# EVSE_Control_and_GFCI.net
KiCad netlist of a schematic drawn in Altium Designer
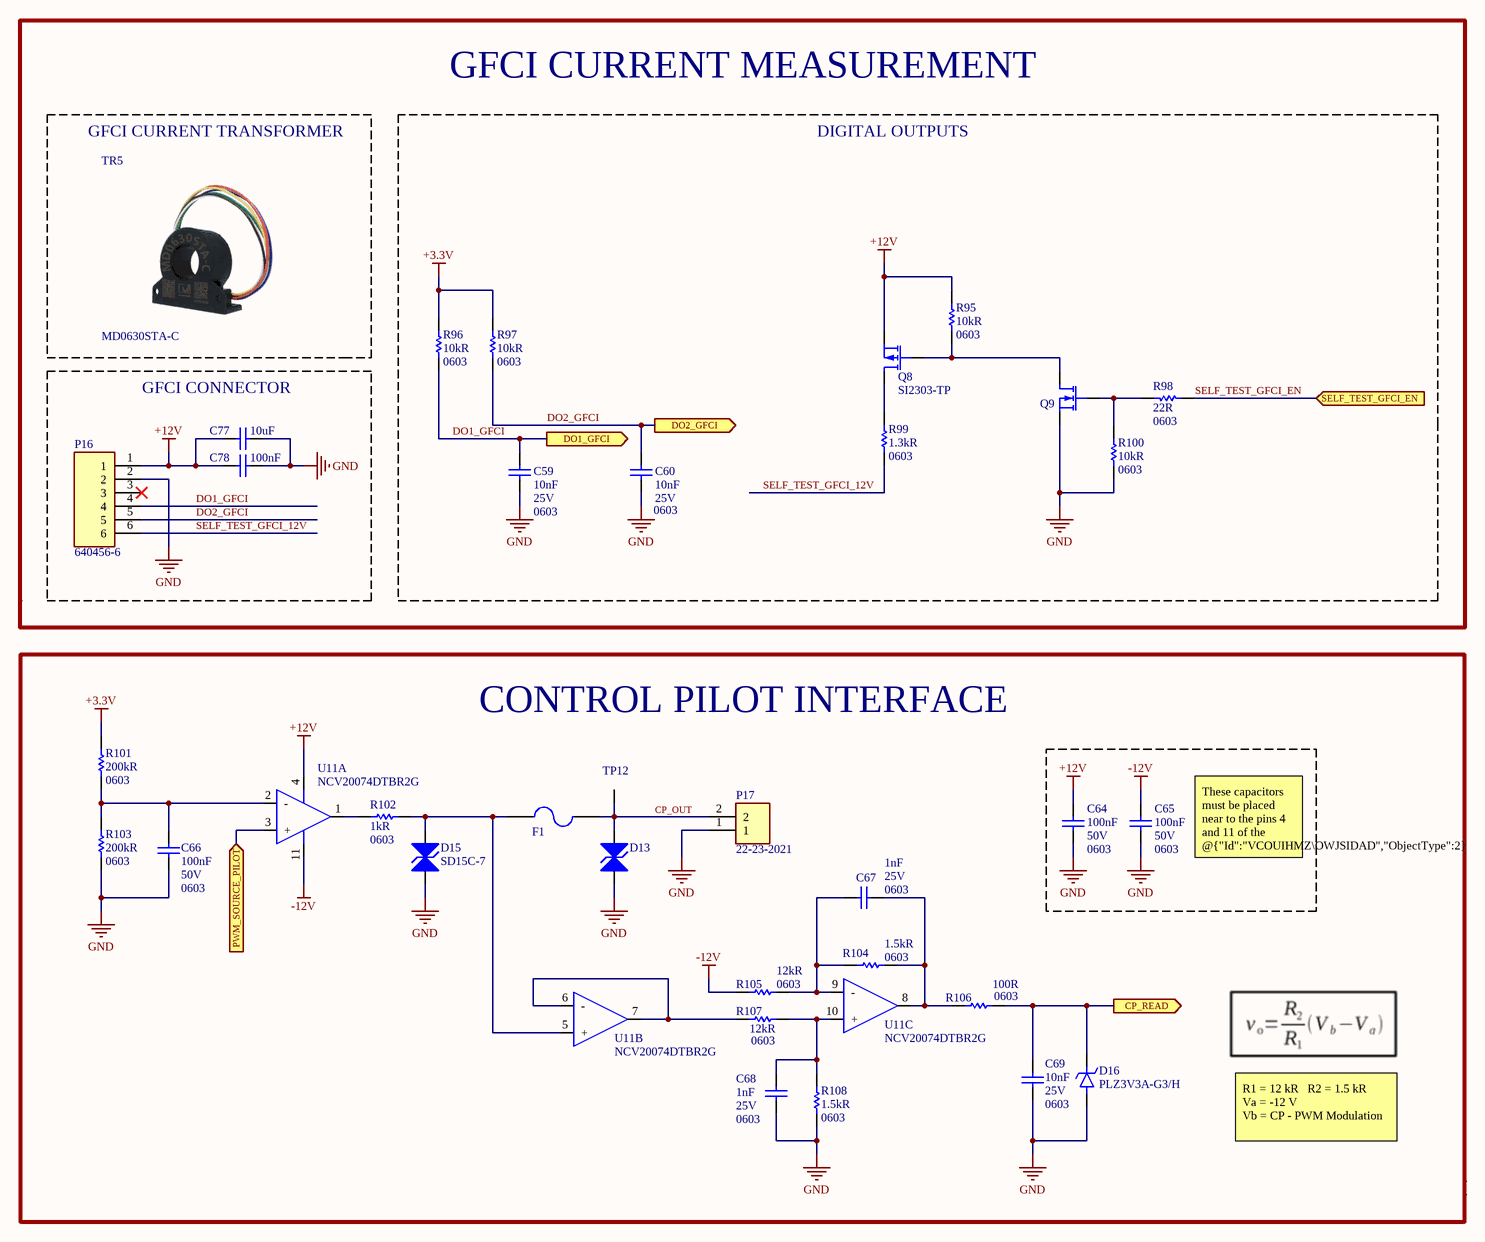
[diagram p0: EVSE Control and GFCI.SchDoc]

(export (version "E")
  (design (tool "Eeschema 10.0.6"))
  (components
    (comp (ref "C59")
      (value "C_0603_0.01uF_25V_10%")
      (footprint "C0603")
      (description "Surface Mount Ceramic Multilayer Capacitor 0.01uF 10% X7R 25V 0603 Paper T/R")
      (fields
        (field (name "MANUFACTURER") "Yageo")
        (field (name "MANUFACTURER PART NUMBER") "CC0603KRX7R8BB103")
        (field (name "VOLTAGE RATING") "25V")
        (field (name "CAPACITANCE") "10nF")
        (field (name "CASE CODE (IMPERIAL)") "0603")
      )
      (libsource (lib "Power2Go - REV05") (part "C_0603_0.01uF_25V_10%"))
    )
    (comp (ref "C60")
      (value "C_0603_0.01uF_25V_10%")
      (footprint "C0603")
      (description "Surface Mount Ceramic Multilayer Capacitor 0.01uF 10% X7R 25V 0603 Paper T/R")
      (fields
        (field (name "MANUFACTURER") "Yageo")
        (field (name "MANUFACTURER PART NUMBER") "CC0603KRX7R8BB103")
        (field (name "VOLTAGE RATING") "25V")
        (field (name "CAPACITANCE") "10nF")
        (field (name "CASE CODE (IMPERIAL)") "0603")
      )
      (libsource (lib "Power2Go - REV05") (part "C_0603_0.01uF_25V_10%"))
    )
    (comp (ref "C64")
      (value "100nF")
      (footprint "C0603")
      (description "Cap Ceramic 50V 20% +Tol 20% -Tol X7R 15% TC 0.1uF SMD 0603")
      (fields
        (field (name "MANUFACTURER") "Yageo")
        (field (name "MANUFACTURER PART NUMBER") "CC0603MRX7R9BB104")
        (field (name "CASE/PACKAGE") "0603")
        (field (name "VOLTAGE RATING") "50V")
      )
      (libsource (lib "Power2Go - REV05") (part "C_0603_0.1uF_50V_20%"))
    )
    (comp (ref "C65")
      (value "100nF")
      (footprint "C0603")
      (description "Cap Ceramic 50V 20% +Tol 20% -Tol X7R 15% TC 0.1uF SMD 0603")
      (fields
        (field (name "MANUFACTURER") "Yageo")
        (field (name "MANUFACTURER PART NUMBER") "CC0603MRX7R9BB104")
        (field (name "CASE/PACKAGE") "0603")
        (field (name "VOLTAGE RATING") "50V")
      )
      (libsource (lib "Power2Go - REV05") (part "C_0603_0.1uF_50V_20%"))
    )
    (comp (ref "C66")
      (value "100nF")
      (footprint "C0603")
      (description "Cap Ceramic 50V 20% +Tol 20% -Tol X7R 15% TC 0.1uF SMD 0603")
      (fields
        (field (name "MANUFACTURER") "Yageo")
        (field (name "MANUFACTURER PART NUMBER") "CC0603MRX7R9BB104")
        (field (name "CASE/PACKAGE") "0603")
        (field (name "VOLTAGE RATING") "50V")
      )
      (libsource (lib "Power2Go - REV05") (part "C_0603_0.1uF_50V_20%"))
    )
    (comp (ref "C67")
      (value "1nF")
      (footprint "C0603")
      (description "0603 C 1nF Ceramic Multilayer Capacitor; 25 VDC; +125degC; C0G Dielectric; +/-5%")
      (fields
        (field (name "MANUFACTURER") "KEMET")
        (field (name "MANUFACTURER PART NUMBER") "C0603C102J3GACTU")
        (field (name "VOLTAGE RATING") "25V")
        (field (name "CASE CODE (IMPERIAL)") "0603")
      )
      (libsource (lib "Power2Go - REV05") (part "C_0603_1000pF_25V_5%"))
    )
    (comp (ref "C68")
      (value "1nF")
      (footprint "C0603")
      (description "0603 C 1nF Ceramic Multilayer Capacitor; 25 VDC; +125degC; C0G Dielectric; +/-5%")
      (fields
        (field (name "MANUFACTURER") "KEMET")
        (field (name "MANUFACTURER PART NUMBER") "C0603C102J3GACTU")
        (field (name "VOLTAGE RATING") "25V")
        (field (name "CASE CODE (IMPERIAL)") "0603")
      )
      (libsource (lib "Power2Go - REV05") (part "C_0603_1000pF_25V_5%"))
    )
    (comp (ref "C69")
      (value "C_0603_0.01uF_25V_10%")
      (footprint "C0603")
      (description "Surface Mount Ceramic Multilayer Capacitor 0.01uF 10% X7R 25V 0603 Paper T/R")
      (fields
        (field (name "MANUFACTURER") "Yageo")
        (field (name "MANUFACTURER PART NUMBER") "CC0603KRX7R8BB103")
        (field (name "VOLTAGE RATING") "25V")
        (field (name "CAPACITANCE") "10nF")
        (field (name "CASE CODE (IMPERIAL)") "0603")
      )
      (libsource (lib "Power2Go - REV05") (part "C_0603_0.01uF_25V_10%"))
    )
    (comp (ref "C77")
      (value "C_0603_10uF_35V_20%")
      (footprint "C0603")
      (description "Cap Ceramic 10uF 35V X5R 20% Pad SMD 0603 85C T/R")
      (fields
        (field (name "MANUFACTURER") "Murata")
        (field (name "MANUFACTURER PART NUMBER") "GRM188R6YA106MA73D")
        (field (name "CAPACITANCE") "10uF")
      )
      (libsource (lib "Power2Go - REV05") (part "C_0603_10uF_35V_20%"))
    )
    (comp (ref "C78")
      (value "100nF")
      (footprint "C0603")
      (description "Cap Ceramic 50V 20% +Tol 20% -Tol X7R 15% TC 0.1uF SMD 0603")
      (fields
        (field (name "MANUFACTURER") "Yageo")
        (field (name "MANUFACTURER PART NUMBER") "CC0603MRX7R9BB104")
      )
      (libsource (lib "Power2Go - REV05") (part "C_0603_0.1uF_50V_20%"))
    )
    (comp (ref "D13")
      (value "SM30T15CAY")
      (footprint "DO-214AB-2")
      (description "Trans Voltage Suppressor Diode, 3000W, 13V V(RWM), Bidirectional, 1 Element, Silicon, DO-214AB")
      (fields (field (name "MANUFACTURER") "STMicroelectronics"))
      (libsource (lib "Power2Go - REV05") (part "D_TVS_SM30T15CAY"))
    )
    (comp (ref "D15")
      (value "SD15C-7")
      (footprint "SOD323")
      (description "TVS Diode Bi-Directional 16.7V 12A 320W 2-Pin SOD-323 T/R")
      (fields (field (name "MANUFACTURER") "Diodes") (field (name "MANUFACTURER PART NUMBER") "SD15C-7"))
      (libsource (lib "Power2Go - REV05") (part "D_TVS_SD15C-7"))
    )
    (comp (ref "D16")
      (value "PLZ3V3A-G3/H")
      (footprint "DO-219AC-2")
      (description "Zener Diode Microsmf Do219Ac2.5%, 3.3V (3.16V - 3.38V), 0.5W")
      (fields (field (name "MANUFACTURER") "Vishay") (field (name "MANUFACTURER PART NUMBER") "PLZ3V3A-G3/H"))
      (libsource (lib "Power2Go - REV05") (part "D_Zenner_PLZ3V3A-G3/H"))
    )
    (comp (ref "F1")
      (value "0ZCM0002FF2G")
      (footprint "F0603")
      (description "PTC Resettable Fuse, 60V, 12ohm, Surface Mount")
      (fields (field (name "MANUFACTURER") "Bel"))
      (libsource (lib "Power2Go - REV05") (part "F_0ZCM0002FF2G_0603"))
    )
    (comp (ref "P16")
      (value "640456-6")
      (footprint "HEADER_2.54MM_6POS_PTH")
      (description "Connector Wire to Board Header 6 Position 2.54mm Solder Straight Thru-Hole")
      (fields
        (field (name "MANUFACTURER") "TE Connectivity")
        (field (name "SUPPLIER PART NUMBER 1") "640456-6")
      )
      (libsource (lib "Power2Go - REV05") (part "P_HEADER_6POS_2.54MM_PTH"))
    )
    (comp (ref "P17")
      (value "22-23-2021")
      (footprint "HEADER_KK_2.54MM_2POS")
      (description "KK 254 Solid Header, Vertical, with Friction Lock, 2 Circuits, Tin (Sn) Plating")
      (fields (field (name "MANUFACTURER") "Molex") (field (name "MANUFACTURER PART NUMBER") "22-23-2021"))
      (libsource (lib "Power2Go - REV05") (part "P_Molex_HEADER_2POS_2.54MM_PTH"))
    )
    (comp (ref "Q8")
      (value "SI2303-TP")
      (footprint "SOT23")
      (description "Sample Fpn Only - P-channel Mosfet, SOT-23 Package")
      (fields (field (name "MANUFACTURER") "MCC") (field (name "MANUFACTURER PART NUMBER") "SI2303-TP"))
      (libsource (lib "Power2Go - REV05") (part "Q_PMOS_SI2303-TP"))
    )
    (comp (ref "Q9")
      (value "RSF015N06FRATL")
      (footprint "TUMT-3")
      (description "Transistor Mosfet N-ch 60V 1.5A 3-PIN Tumt T/r")
      (fields (field (name "MANUFACTURER") "Rohm"))
      (libsource (lib "Power2Go - REV05") (part "Q_RSF015N06FRATL_TUMT-3"))
    )
    (comp (ref "R95")
      (value "10kR")
      (footprint "R0603")
      (fields
        (field (name "MANUFACTURER") "Vishay")
        (field (name "MANUFACTURER PART NUMBER") "CRCW060310K0JNEBC")
        (field (name "TOLERANCE") "5%")
        (field (name "CASE/PACKAGE") "0603")
      )
      (libsource (lib "Power2Go - REV05") (part "R_0603_10kR_5%_1/10W"))
    )
    (comp (ref "R96")
      (value "10kR")
      (footprint "R0603")
      (fields
        (field (name "MANUFACTURER") "Vishay")
        (field (name "MANUFACTURER PART NUMBER") "CRCW060310K0JNEBC")
        (field (name "TOLERANCE") "5%")
        (field (name "CASE/PACKAGE") "0603")
      )
      (libsource (lib "Power2Go - REV05") (part "R_0603_10kR_5%_1/10W"))
    )
    (comp (ref "R97")
      (value "10kR")
      (footprint "R0603")
      (fields
        (field (name "MANUFACTURER") "Vishay")
        (field (name "MANUFACTURER PART NUMBER") "CRCW060310K0JNEBC")
        (field (name "TOLERANCE") "5%")
        (field (name "CASE/PACKAGE") "0603")
      )
      (libsource (lib "Power2Go - REV05") (part "R_0603_10kR_5%_1/10W"))
    )
    (comp (ref "R98")
      (value "CRCW060322R0FKEAC")
      (footprint "R0603")
      (description "Thick Film Resistors - SMD 1/10Watt 22ohms 1% Commercial Use")
      (fields
        (field (name "MANUFACTURER") "Vishay")
        (field (name "TOLERANCE") "1%")
        (field (name "RESISTANCE") "22R")
        (field (name "CASE CODE (IMPERIAL)") "0603")
      )
      (libsource (lib "Power2Go - REV05") (part "R_0603_22R_1%_1/10W"))
    )
    (comp (ref "R99")
      (value "1.3kR")
      (footprint "R0603")
      (description "SMD Chip Resistor, 1.3 kOhm, ± 1%, 250 mW, 0603 [1608 Metric], Thick Film, Anti-Surge")
      (fields
        (field (name "MANUFACTURER") "Panasonic")
        (field (name "TOLERANCE") "1%")
        (field (name "CASE CODE (IMPERIAL)") "0603")
      )
      (libsource (lib "Power2Go - REV05") (part "R_0603_1.3kR_1%_1/4W"))
    )
    (comp (ref "R100")
      (value "10kR")
      (footprint "R0603")
      (fields
        (field (name "MANUFACTURER") "Vishay")
        (field (name "MANUFACTURER PART NUMBER") "CRCW060310K0JNEBC")
        (field (name "TOLERANCE") "5%")
        (field (name "CASE/PACKAGE") "0603")
      )
      (libsource (lib "Power2Go - REV05") (part "R_0603_10kR_5%_1/10W"))
    )
    (comp (ref "R101")
      (value "200kR")
      (footprint "R0603")
      (description "Res Thin Film 0603 200K Ohm 1% 1/10W ±25ppm/°C Molded SMD Paper T/R")
      (fields
        (field (name "MANUFACTURER") "Yageo")
        (field (name "MANUFACTURER PART NUMBER") "RT0603FRD07200KL")
        (field (name "CASE/PACKAGE") "0603")
      )
      (libsource (lib "Power2Go - REV05") (part "R_0603_200kR_1%_1/10W_25PPM"))
    )
    (comp (ref "R102")
      (value "1kR")
      (footprint "R0603")
      (description "RES SMD 1K OHM 1% 1/10W 0603")
      (fields
        (field (name "MANUFACTURER") "Bourns")
        (field (name "MANUFACTURER PART NUMBER") "CRT0603-FY-1001ELF")
        (field (name "CASE/PACKAGE") "0603")
      )
      (libsource (lib "Power2Go - REV05") (part "R_0603_1kR_1%_1/10W_25PPM"))
    )
    (comp (ref "R103")
      (value "200kR")
      (footprint "R0603")
      (description "Res Thin Film 0603 200K Ohm 1% 1/10W ±25ppm/°C Molded SMD Paper T/R")
      (fields
        (field (name "MANUFACTURER") "Yageo")
        (field (name "MANUFACTURER PART NUMBER") "RT0603FRD07200KL")
        (field (name "CASE/PACKAGE") "0603")
      )
      (libsource (lib "Power2Go - REV05") (part "R_0603_200kR_1%_1/10W_25PPM"))
    )
    (comp (ref "R104")
      (value "1.5kR")
      (footprint "R0603")
      (description "Res 1.5K Ohm 1% 1/10W 0603")
      (fields
        (field (name "MANUFACTURER") "KOA Speer")
        (field (name "MANUFACTURER PART NUMBER") "RN73H1JTTD1501F25")
        (field (name "CASE CODE (IMPERIAL)") "0603")
      )
      (libsource (lib "Power2Go - REV05") (part "R_0603_1.5kR_1%_1/10W_25PPM"))
    )
    (comp (ref "R105")
      (value "12kR")
      (footprint "R0603")
      (description "Res Thin Film 0603 12K Ohm 0.5% 1/10W ±25ppm/°C Molded SMD SMD Paper T/R")
      (fields
        (field (name "MANUFACTURER") "Yageo")
        (field (name "MANUFACTURER PART NUMBER") "RT0603DRD0712KL")
        (field (name "CASE CODE (IMPERIAL)") "0603")
      )
      (libsource (lib "Power2Go - REV05") (part "R_0603_12kR_0.5%_1/10W_25PPM"))
    )
    (comp (ref "R106")
      (value "100R")
      (footprint "R0603")
      (description "Res Thin Film 0603 100 Ohm 1% 1/10W ±25ppm/°C Molded SMD Paper Tape on Plastic Reel")
      (fields
        (field (name "MANUFACTURER") "Bourns")
        (field (name "MANUFACTURER PART NUMBER") "CRT0603-FY-1000ELF")
        (field (name "CASE/PACKAGE") "0603")
      )
      (libsource (lib "Power2Go - REV05") (part "R_0603_100R_1%_1/10W_25PPM"))
    )
    (comp (ref "R107")
      (value "12kR")
      (footprint "R0603")
      (description "Res Thin Film 0603 12K Ohm 0.5% 1/10W ±25ppm/°C Molded SMD SMD Paper T/R")
      (fields
        (field (name "MANUFACTURER") "Yageo")
        (field (name "MANUFACTURER PART NUMBER") "RT0603DRD0712KL")
        (field (name "CASE CODE (IMPERIAL)") "0603")
      )
      (libsource (lib "Power2Go - REV05") (part "R_0603_12kR_0.5%_1/10W_25PPM"))
    )
    (comp (ref "R108")
      (value "1.5kR")
      (footprint "R0603")
      (description "Res 1.5K Ohm 1% 1/10W 0603")
      (fields
        (field (name "MANUFACTURER") "KOA Speer")
        (field (name "MANUFACTURER PART NUMBER") "RN73H1JTTD1501F25")
        (field (name "CASE CODE (IMPERIAL)") "0603")
      )
      (libsource (lib "Power2Go - REV05") (part "R_0603_1.5kR_1%_1/10W_25PPM"))
    )
    (comp (ref "TP12")
      (value "S2761-46R")
      (footprint "TP_S276146R")
      (fields (field (name "MANUFACTURER") "Harwin"))
      (libsource (lib "Power2Go - REV05") (part "TP_S2761-46R_SMT"))
    )
    (comp (ref "TR5")
      (value "MD0630STA-C")
      (footprint "TC_MD0630STA-C")
      (description "MD36da-P Costly Evse B-Type RCD CT 6mA DC Residual Direct Current Detecting Device Sensor")
      (fields (field (name "MANUFACTER PART NUMBER") "MD0630STA-C"))
      (libsource (lib "Power2Go - REV05") (part "TR_MD0630STA-C"))
    )
    (comp (ref "U11")
      (value "NCV20074DTBR2G")
      (footprint "TSSOP-14")
      (description "Operational Amplifier, Wide supply range, 3 MHz CMOS Op-Amp")
      (fields
        (field (name "MANUFACTURER") "ON Semiconductor")
        (field (name "SUPPLIER PART NUMBER 1") "NCV20074DTBR2G")
      )
      (libsource (lib "Power2Go - REV05") (part "U_NCV20074DTBR2G_TSSOP-14"))
    )
  )
  (nets
    (net (code "1") (name "+3.3V") (class "Default")
      (node (ref "R101") (pin "1") (pinfunction "1_1") (pintype "passive"))
      (node (ref "R96") (pin "2") (pinfunction "2_2") (pintype "passive"))
      (node (ref "R97") (pin "2") (pinfunction "2_2") (pintype "passive"))
    )
    (net (code "2") (name "+12V") (class "Default")
      (node (ref "C64") (pin "1") (pinfunction "1_1") (pintype "passive"))
      (node (ref "C77") (pin "2") (pinfunction "2_2") (pintype "passive"))
      (node (ref "C78") (pin "2") (pinfunction "2_2") (pintype "passive"))
      (node (ref "P16") (pin "1") (pinfunction "1_1") (pintype "passive"))
      (node (ref "Q8") (pin "2") (pinfunction "S_2") (pintype "passive"))
      (node (ref "R95") (pin "2") (pinfunction "2_2") (pintype "passive"))
      (node (ref "U11") (pin "4") (pinfunction "V+_4") (pintype "passive"))
    )
    (net (code "3") (name "-12V") (class "Default")
      (node (ref "C65") (pin "1") (pinfunction "1_1") (pintype "passive"))
      (node (ref "R105") (pin "1") (pinfunction "1_1") (pintype "passive"))
      (node (ref "U11") (pin "11") (pinfunction "V-_11") (pintype "passive"))
    )
    (net (code "4") (name "/CP_OUT") (class "Default")
      (node (ref "D13") (pin "2") (pinfunction "2_2") (pintype "passive"))
      (node (ref "F1") (pin "2") (pinfunction "2_2") (pintype "passive"))
      (node (ref "P17") (pin "2") (pinfunction "2_2") (pintype "passive"))
      (node (ref "TP12") (pin "1") (pinfunction "1_1") (pintype "passive"))
    )
    (net (code "5") (name "/CP_READ") (class "Default")
      (node (ref "C69") (pin "1") (pinfunction "1_1") (pintype "passive"))
      (node (ref "D16") (pin "1") (pinfunction "K_1") (pintype "passive"))
      (node (ref "R106") (pin "2") (pinfunction "2_2") (pintype "passive"))
    )
    (net (code "6") (name "/DO1_GFCI") (class "Default")
      (node (ref "C59") (pin "2") (pinfunction "2_2") (pintype "passive"))
      (node (ref "P16") (pin "4") (pinfunction "4_4") (pintype "passive"))
      (node (ref "R96") (pin "1") (pinfunction "1_1") (pintype "passive"))
    )
    (net (code "7") (name "/DO2_GFCI") (class "Default")
      (node (ref "C60") (pin "2") (pinfunction "2_2") (pintype "passive"))
      (node (ref "P16") (pin "5") (pinfunction "5_5") (pintype "passive"))
      (node (ref "R97") (pin "1") (pinfunction "1_1") (pintype "passive"))
    )
    (net (code "8") (name "/PWM_SOURCE_PILOT") (class "Default")
      (node (ref "U11") (pin "3") (pinfunction "+_3") (pintype "passive"))
    )
    (net (code "9") (name "/SELF_TEST_GFCI_12V") (class "Default")
      (node (ref "P16") (pin "6") (pinfunction "6_6") (pintype "passive"))
      (node (ref "R99") (pin "1") (pinfunction "1_1") (pintype "passive"))
    )
    (net (code "10") (name "/SELF_TEST_GFCI_EN") (class "Default")
      (node (ref "R98") (pin "2") (pinfunction "2_2") (pintype "passive"))
    )
    (net (code "11") (name "GND") (class "Default")
      (node (ref "C59") (pin "1") (pinfunction "1_1") (pintype "passive"))
      (node (ref "C60") (pin "1") (pinfunction "1_1") (pintype "passive"))
      (node (ref "C64") (pin "2") (pinfunction "2_2") (pintype "passive"))
      (node (ref "C65") (pin "2") (pinfunction "2_2") (pintype "passive"))
      (node (ref "C66") (pin "2") (pinfunction "2_2") (pintype "passive"))
      (node (ref "C68") (pin "1") (pinfunction "1_1") (pintype "passive"))
      (node (ref "C69") (pin "2") (pinfunction "2_2") (pintype "passive"))
      (node (ref "C77") (pin "1") (pinfunction "1_1") (pintype "passive"))
      (node (ref "C78") (pin "1") (pinfunction "1_1") (pintype "passive"))
      (node (ref "D13") (pin "1") (pinfunction "1_1") (pintype "passive"))
      (node (ref "D15") (pin "1") (pinfunction "1_1") (pintype "passive"))
      (node (ref "D16") (pin "2") (pinfunction "A_2") (pintype "passive"))
      (node (ref "P16") (pin "2") (pinfunction "2_2") (pintype "passive"))
      (node (ref "P17") (pin "1") (pinfunction "1_1") (pintype "passive"))
      (node (ref "Q9") (pin "2") (pinfunction "S_2") (pintype "passive"))
      (node (ref "R100") (pin "1") (pinfunction "1_1") (pintype "passive"))
      (node (ref "R103") (pin "2") (pinfunction "2_2") (pintype "passive"))
      (node (ref "R108") (pin "2") (pinfunction "2_2") (pintype "passive"))
    )
    (net (code "12") (name "Net-(Q8-D)") (class "Default")
      (node (ref "Q8") (pin "3") (pinfunction "D_3") (pintype "passive"))
      (node (ref "R99") (pin "2") (pinfunction "2_2") (pintype "passive"))
    )
    (net (code "13") (name "Net-(Q8-G)") (class "Default")
      (node (ref "Q8") (pin "1") (pinfunction "G_1") (pintype "passive"))
      (node (ref "Q9") (pin "3") (pinfunction "D_3") (pintype "passive"))
      (node (ref "R95") (pin "1") (pinfunction "1_1") (pintype "passive"))
    )
    (net (code "14") (name "Net-(Q9-G)") (class "Default")
      (node (ref "Q9") (pin "1") (pinfunction "G_1") (pintype "passive"))
      (node (ref "R100") (pin "2") (pinfunction "2_2") (pintype "passive"))
      (node (ref "R98") (pin "1") (pinfunction "1_1") (pintype "passive"))
    )
    (net (code "15") (name "Net-(U11A--)") (class "Default")
      (node (ref "C66") (pin "1") (pinfunction "1_1") (pintype "passive"))
      (node (ref "R101") (pin "2") (pinfunction "2_2") (pintype "passive"))
      (node (ref "R103") (pin "1") (pinfunction "1_1") (pintype "passive"))
      (node (ref "U11") (pin "2") (pinfunction "-_2") (pintype "passive"))
    )
    (net (code "16") (name "Net-(U11A-OUT_A)") (class "Default")
      (node (ref "R102") (pin "2") (pinfunction "2_2") (pintype "passive"))
      (node (ref "U11") (pin "1") (pinfunction "OUT_A_1") (pintype "passive"))
    )
    (net (code "17") (name "Net-(U11B-+)") (class "Default")
      (node (ref "D15") (pin "2") (pinfunction "2_2") (pintype "passive"))
      (node (ref "F1") (pin "1") (pinfunction "1_1") (pintype "passive"))
      (node (ref "R102") (pin "1") (pinfunction "1_1") (pintype "passive"))
      (node (ref "U11") (pin "5") (pinfunction "+_5") (pintype "passive"))
    )
    (net (code "18") (name "Net-(U11B--)") (class "Default")
      (node (ref "R107") (pin "1") (pinfunction "1_1") (pintype "passive"))
      (node (ref "U11") (pin "6") (pinfunction "-_6") (pintype "passive"))
      (node (ref "U11") (pin "7") (pinfunction "OUT_B_7") (pintype "passive"))
    )
    (net (code "19") (name "Net-(U11C-+)") (class "Default")
      (node (ref "C68") (pin "2") (pinfunction "2_2") (pintype "passive"))
      (node (ref "R107") (pin "2") (pinfunction "2_2") (pintype "passive"))
      (node (ref "R108") (pin "1") (pinfunction "1_1") (pintype "passive"))
      (node (ref "U11") (pin "10") (pinfunction "+_10") (pintype "passive"))
    )
    (net (code "20") (name "Net-(U11C--)") (class "Default")
      (node (ref "C67") (pin "2") (pinfunction "2_2") (pintype "passive"))
      (node (ref "R104") (pin "1") (pinfunction "1_1") (pintype "passive"))
      (node (ref "R105") (pin "2") (pinfunction "2_2") (pintype "passive"))
      (node (ref "U11") (pin "9") (pinfunction "-_9") (pintype "passive"))
    )
    (net (code "21") (name "Net-(U11C-OUT_C)") (class "Default")
      (node (ref "C67") (pin "1") (pinfunction "1_1") (pintype "passive"))
      (node (ref "R104") (pin "2") (pinfunction "2_2") (pintype "passive"))
      (node (ref "R106") (pin "1") (pinfunction "1_1") (pintype "passive"))
      (node (ref "U11") (pin "8") (pinfunction "OUT_C_8") (pintype "passive"))
    )
    (net (code "22") (name "unconnected-(P16-Pad3)") (class "Default")
      (node (ref "P16") (pin "3") (pinfunction "3_3") (pintype "passive+no_connect"))
    )
  )
)
